# NEO6MV2.net
KiCad netlist of a schematic drawn in Altium Designer
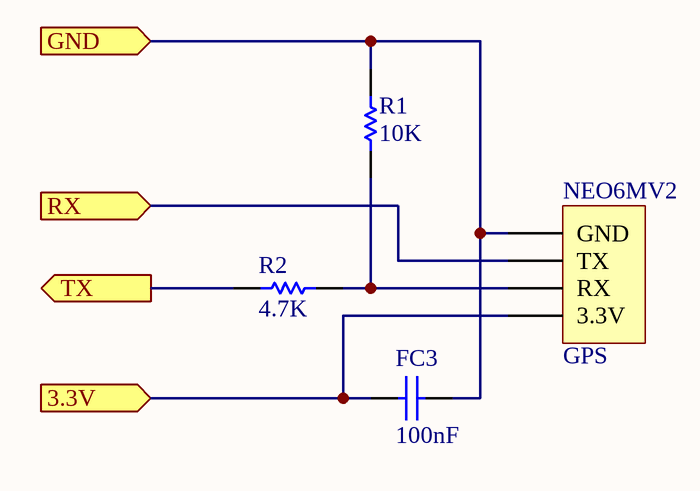
[diagram p0: NEO6MV2.SchDoc]

(export (version "E")
  (design (tool "Eeschema 10.0.6"))
  (components
    (comp (ref "FC3")
      (value "100nF")
      (footprint "RAD-0.3")
      (description "Capacitor")
      (fields (field (name "PUBLISHER") "Altium Limited"))
      (libsource (lib "Miscellaneous Devices") (part "Cap"))
    )
    (comp (ref "NEO6MV2")
      (value "GPS")
      (footprint "HDR1X4")
      (description "Header, 4-Pin")
      (fields (field (name "PUBLISHER") "Altium Limited"))
      (libsource (lib "Miscellaneous Connectors") (part "Header 4"))
    )
    (comp (ref "R1")
      (value "10K")
      (footprint "AXIAL-0.3")
      (description "Resistor")
      (fields (field (name "PUBLISHER") "Altium Limited"))
      (libsource (lib "Miscellaneous Devices") (part "Res1"))
    )
    (comp (ref "R2")
      (value "4.7K")
      (footprint "AXIAL-0.3")
      (description "Resistor")
      (fields (field (name "PUBLISHER") "Altium Limited"))
      (libsource (lib "Miscellaneous Devices") (part "Res1"))
    )
  )
  (nets
    (net (code "1") (name "/3.3V") (class "Default")
      (node (ref "FC3") (pin "1") (pinfunction "1_1") (pintype "passive"))
      (node (ref "NEO6MV2") (pin "4") (pinfunction "3.3V_4") (pintype "passive"))
    )
    (net (code "2") (name "/GND") (class "Default")
      (node (ref "FC3") (pin "2") (pinfunction "2_2") (pintype "passive"))
      (node (ref "NEO6MV2") (pin "1") (pinfunction "GND_1") (pintype "passive"))
      (node (ref "R1") (pin "2") (pinfunction "2_2") (pintype "passive"))
    )
    (net (code "3") (name "/RX") (class "Default")
      (node (ref "NEO6MV2") (pin "2") (pinfunction "TX_2") (pintype "passive"))
    )
    (net (code "4") (name "/TX") (class "Default")
      (node (ref "R2") (pin "1") (pinfunction "1_1") (pintype "passive"))
    )
    (net (code "5") (name "Net-(NEO6MV2-RX)") (class "Default")
      (node (ref "NEO6MV2") (pin "3") (pinfunction "RX_3") (pintype "passive"))
      (node (ref "R1") (pin "1") (pinfunction "1_1") (pintype "passive"))
      (node (ref "R2") (pin "2") (pinfunction "2_2") (pintype "passive"))
    )
  )
)
